# GPS_modul.net
KiCad netlist of a schematic drawn in EAGLE
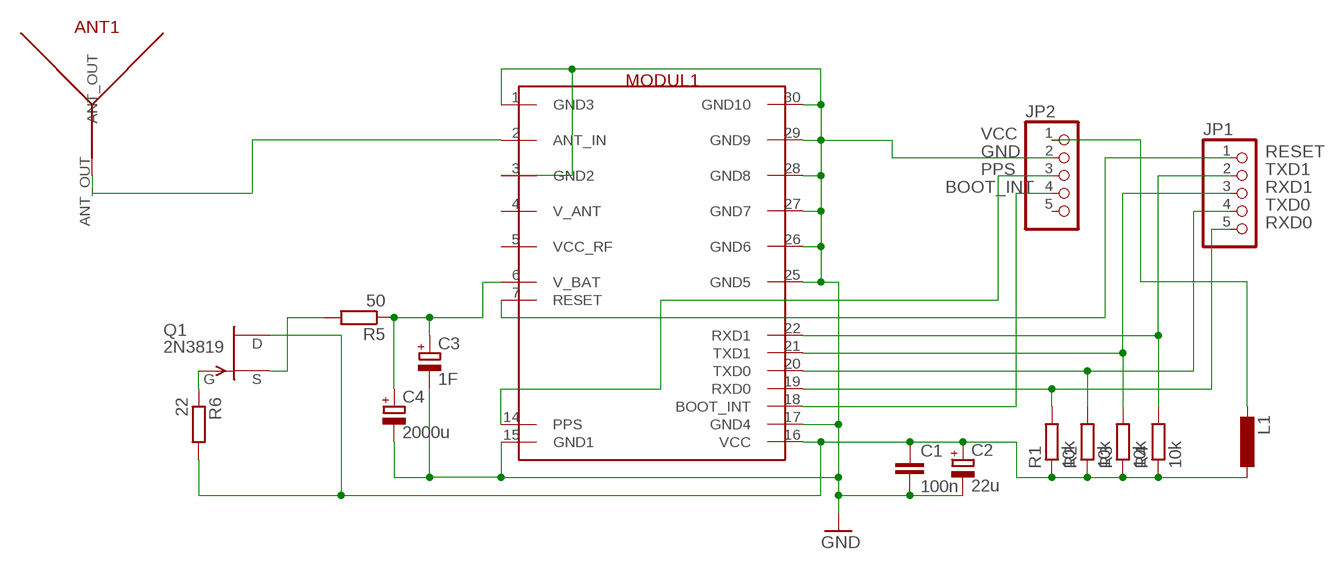
[diagram p0: schematic, sheet 1]

(export (version "E")
  (design (tool "Eeschema 10.0.6"))
  (components
    (comp (ref "ANT1")
      (value "GPS_ANTDEFAULT")
      (footprint "eagle-import:GPS_ANT_CERAMIC")
      (libsource (lib "eagle-import") (part "GPS_ANTDEFAULT"))
    )
    (comp (ref "C1")
      (value "100n")
      (footprint "eagle-import:C0805K")
      (libsource (lib "eagle-import") (part "C-EUC0805K"))
    )
    (comp (ref "C2")
      (value "22u")
      (footprint "eagle-import:153CLV-0605")
      (libsource (lib "eagle-import") (part "CPOL-EU153CLV-0605"))
    )
    (comp (ref "C3")
      (value "1F")
      (footprint "eagle-import:EB20D")
      (libsource (lib "eagle-import") (part "CPOL-EUE10-20"))
    )
    (comp (ref "C4")
      (value "2000u")
      (footprint "eagle-import:EB20D")
      (libsource (lib "eagle-import") (part "CPOL-EUE10-20"))
    )
    (comp (ref "JP1")
      (value "PINHD-1X5")
      (footprint "eagle-import:1X05")
      (libsource (lib "eagle-import") (part "PINHD-1X5"))
    )
    (comp (ref "JP2")
      (value "PINHD-1X5")
      (footprint "eagle-import:1X05")
      (libsource (lib "eagle-import") (part "PINHD-1X5"))
    )
    (comp (ref "L1")
      (value "L-EUL3225P")
      (footprint "eagle-import:L3225P")
      (libsource (lib "eagle-import") (part "L-EUL3225P"))
    )
    (comp (ref "MODUL1")
      (value "SKYNAV_GM25DEFAULT")
      (footprint "eagle-import:SMD_SKYNAV_GM25")
      (libsource (lib "eagle-import") (part "SKYNAV_GM25DEFAULT"))
    )
    (comp (ref "Q1")
      (value "2N3819")
      (footprint "eagle-import:TO92")
      (libsource (lib "eagle-import") (part "2N3819"))
    )
    (comp (ref "R1")
      (value "10k")
      (footprint "eagle-import:R1206")
      (libsource (lib "eagle-import") (part "R-EU_R1206"))
    )
    (comp (ref "R2")
      (value "10k")
      (footprint "eagle-import:R1206")
      (libsource (lib "eagle-import") (part "R-EU_R1206"))
    )
    (comp (ref "R3")
      (value "10k")
      (footprint "eagle-import:R1206")
      (libsource (lib "eagle-import") (part "R-EU_R1206"))
    )
    (comp (ref "R4")
      (value "10k")
      (footprint "eagle-import:R1206")
      (libsource (lib "eagle-import") (part "R-EU_R1206"))
    )
    (comp (ref "R5")
      (value "50")
      (footprint "eagle-import:0204_7")
      (libsource (lib "eagle-import") (part "R-EU_0204/7"))
    )
    (comp (ref "R6")
      (value "22")
      (footprint "eagle-import:0204_7")
      (libsource (lib "eagle-import") (part "R-EU_0204/7"))
    )
  )
  (nets
    (net (code "1") (name "/BOOT_INT") (class "Default")
      (node (ref "JP2") (pin "4") (pinfunction "4_4") (pintype "passive"))
      (node (ref "MODUL1") (pin "18") (pinfunction "BOOT_INT_18") (pintype "bidirectional"))
    )
    (net (code "2") (name "/PPS") (class "Default")
      (node (ref "JP2") (pin "3") (pinfunction "3_3") (pintype "passive"))
      (node (ref "MODUL1") (pin "14") (pinfunction "PPS_14") (pintype "bidirectional"))
    )
    (net (code "3") (name "/RESET") (class "Default")
      (node (ref "JP1") (pin "1") (pinfunction "1_1") (pintype "passive"))
      (node (ref "MODUL1") (pin "7") (pinfunction "RESET_7") (pintype "bidirectional"))
    )
    (net (code "4") (name "/RXD0") (class "Default")
      (node (ref "JP1") (pin "5") (pinfunction "5_5") (pintype "passive"))
      (node (ref "MODUL1") (pin "19") (pinfunction "RXD0_19") (pintype "bidirectional"))
      (node (ref "R1") (pin "2") (pinfunction "2_2") (pintype "passive"))
    )
    (net (code "5") (name "/RXD1") (class "Default")
      (node (ref "JP1") (pin "2") (pinfunction "2_2") (pintype "passive"))
      (node (ref "MODUL1") (pin "22") (pinfunction "RXD1_22") (pintype "bidirectional"))
      (node (ref "R4") (pin "2") (pinfunction "2_2") (pintype "passive"))
    )
    (net (code "6") (name "/TXD0") (class "Default")
      (node (ref "JP1") (pin "4") (pinfunction "4_4") (pintype "passive"))
      (node (ref "MODUL1") (pin "20") (pinfunction "TXD0_20") (pintype "bidirectional"))
      (node (ref "R2") (pin "2") (pinfunction "2_2") (pintype "passive"))
    )
    (net (code "7") (name "/TXD1") (class "Default")
      (node (ref "JP1") (pin "3") (pinfunction "3_3") (pintype "passive"))
      (node (ref "MODUL1") (pin "21") (pinfunction "TXD1_21") (pintype "bidirectional"))
      (node (ref "R3") (pin "2") (pinfunction "2_2") (pintype "passive"))
    )
    (net (code "8") (name "/VCC") (class "Default")
      (node (ref "JP2") (pin "1") (pinfunction "1_1") (pintype "passive"))
      (node (ref "L1") (pin "2") (pinfunction "2_2") (pintype "passive"))
    )
    (net (code "9") (name "GND") (class "Default")
      (node (ref "C1") (pin "2") (pinfunction "2_2") (pintype "passive"))
      (node (ref "C2") (pin "-") (pinfunction "-_-") (pintype "passive"))
      (node (ref "C3") (pin "-") (pinfunction "-_-") (pintype "passive"))
      (node (ref "C4") (pin "-") (pinfunction "-_-") (pintype "passive"))
      (node (ref "JP2") (pin "2") (pinfunction "2_2") (pintype "passive"))
      (node (ref "MODUL1") (pin "1") (pinfunction "GND3_1") (pintype "bidirectional"))
      (node (ref "MODUL1") (pin "15") (pinfunction "GND1_15") (pintype "bidirectional"))
      (node (ref "MODUL1") (pin "17") (pinfunction "GND4_17") (pintype "bidirectional"))
      (node (ref "MODUL1") (pin "25") (pinfunction "GND5_25") (pintype "bidirectional"))
      (node (ref "MODUL1") (pin "26") (pinfunction "GND6_26") (pintype "bidirectional"))
      (node (ref "MODUL1") (pin "27") (pinfunction "GND7_27") (pintype "bidirectional"))
      (node (ref "MODUL1") (pin "28") (pinfunction "GND8_28") (pintype "bidirectional"))
      (node (ref "MODUL1") (pin "29") (pinfunction "GND9_29") (pintype "bidirectional"))
      (node (ref "MODUL1") (pin "3") (pinfunction "GND2_3") (pintype "bidirectional"))
      (node (ref "MODUL1") (pin "30") (pinfunction "GND10_30") (pintype "bidirectional"))
    )
    (net (code "10") (name "Net-(MODUL1-ANT_IN)") (class "Default")
      (node (ref "ANT1") (pin "ANT_OUT") (pinfunction "ANT_OUT_ANT_OUT") (pintype "bidirectional"))
      (node (ref "MODUL1") (pin "2") (pinfunction "ANT_IN_2") (pintype "bidirectional"))
    )
    (net (code "11") (name "Net-(MODUL1-VCC)") (class "Default")
      (node (ref "C1") (pin "1") (pinfunction "1_1") (pintype "passive"))
      (node (ref "C2") (pin "+") (pinfunction "+_+") (pintype "passive"))
      (node (ref "L1") (pin "1") (pinfunction "1_1") (pintype "passive"))
      (node (ref "MODUL1") (pin "16") (pinfunction "VCC_16") (pintype "bidirectional"))
      (node (ref "Q1") (pin "1") (pinfunction "D_1") (pintype "passive"))
      (node (ref "R1") (pin "1") (pinfunction "1_1") (pintype "passive"))
      (node (ref "R2") (pin "1") (pinfunction "1_1") (pintype "passive"))
      (node (ref "R3") (pin "1") (pinfunction "1_1") (pintype "passive"))
      (node (ref "R4") (pin "1") (pinfunction "1_1") (pintype "passive"))
      (node (ref "R6") (pin "2") (pinfunction "2_2") (pintype "passive"))
    )
    (net (code "12") (name "Net-(MODUL1-V_BAT)") (class "Default")
      (node (ref "C3") (pin "+") (pinfunction "+_+") (pintype "passive"))
      (node (ref "C4") (pin "+") (pinfunction "+_+") (pintype "passive"))
      (node (ref "MODUL1") (pin "6") (pinfunction "V_BAT_6") (pintype "bidirectional"))
      (node (ref "R5") (pin "1") (pinfunction "1_1") (pintype "passive"))
    )
    (net (code "13") (name "Net-(Q1-G)") (class "Default")
      (node (ref "Q1") (pin "2") (pinfunction "G_2") (pintype "passive"))
      (node (ref "R6") (pin "1") (pinfunction "1_1") (pintype "passive"))
    )
    (net (code "14") (name "Net-(Q1-S)") (class "Default")
      (node (ref "Q1") (pin "3") (pinfunction "S_3") (pintype "passive"))
      (node (ref "R5") (pin "2") (pinfunction "2_2") (pintype "passive"))
    )
    (net (code "15") (name "unconnected-(JP2-Pad5)") (class "Default")
      (node (ref "JP2") (pin "5") (pinfunction "5_5") (pintype "passive"))
    )
    (net (code "16") (name "unconnected-(MODUL1-VCC_RF-Pad5)") (class "Default")
      (node (ref "MODUL1") (pin "5") (pinfunction "VCC_RF_5") (pintype "bidirectional"))
    )
    (net (code "17") (name "unconnected-(MODUL1-V_ANT-Pad4)") (class "Default")
      (node (ref "MODUL1") (pin "4") (pinfunction "V_ANT_4") (pintype "bidirectional"))
    )
  )
)
